# Radio_Robotic_GloveBox_Manipulator.net
KiCad netlist of a schematic drawn in EasyEDA Pro
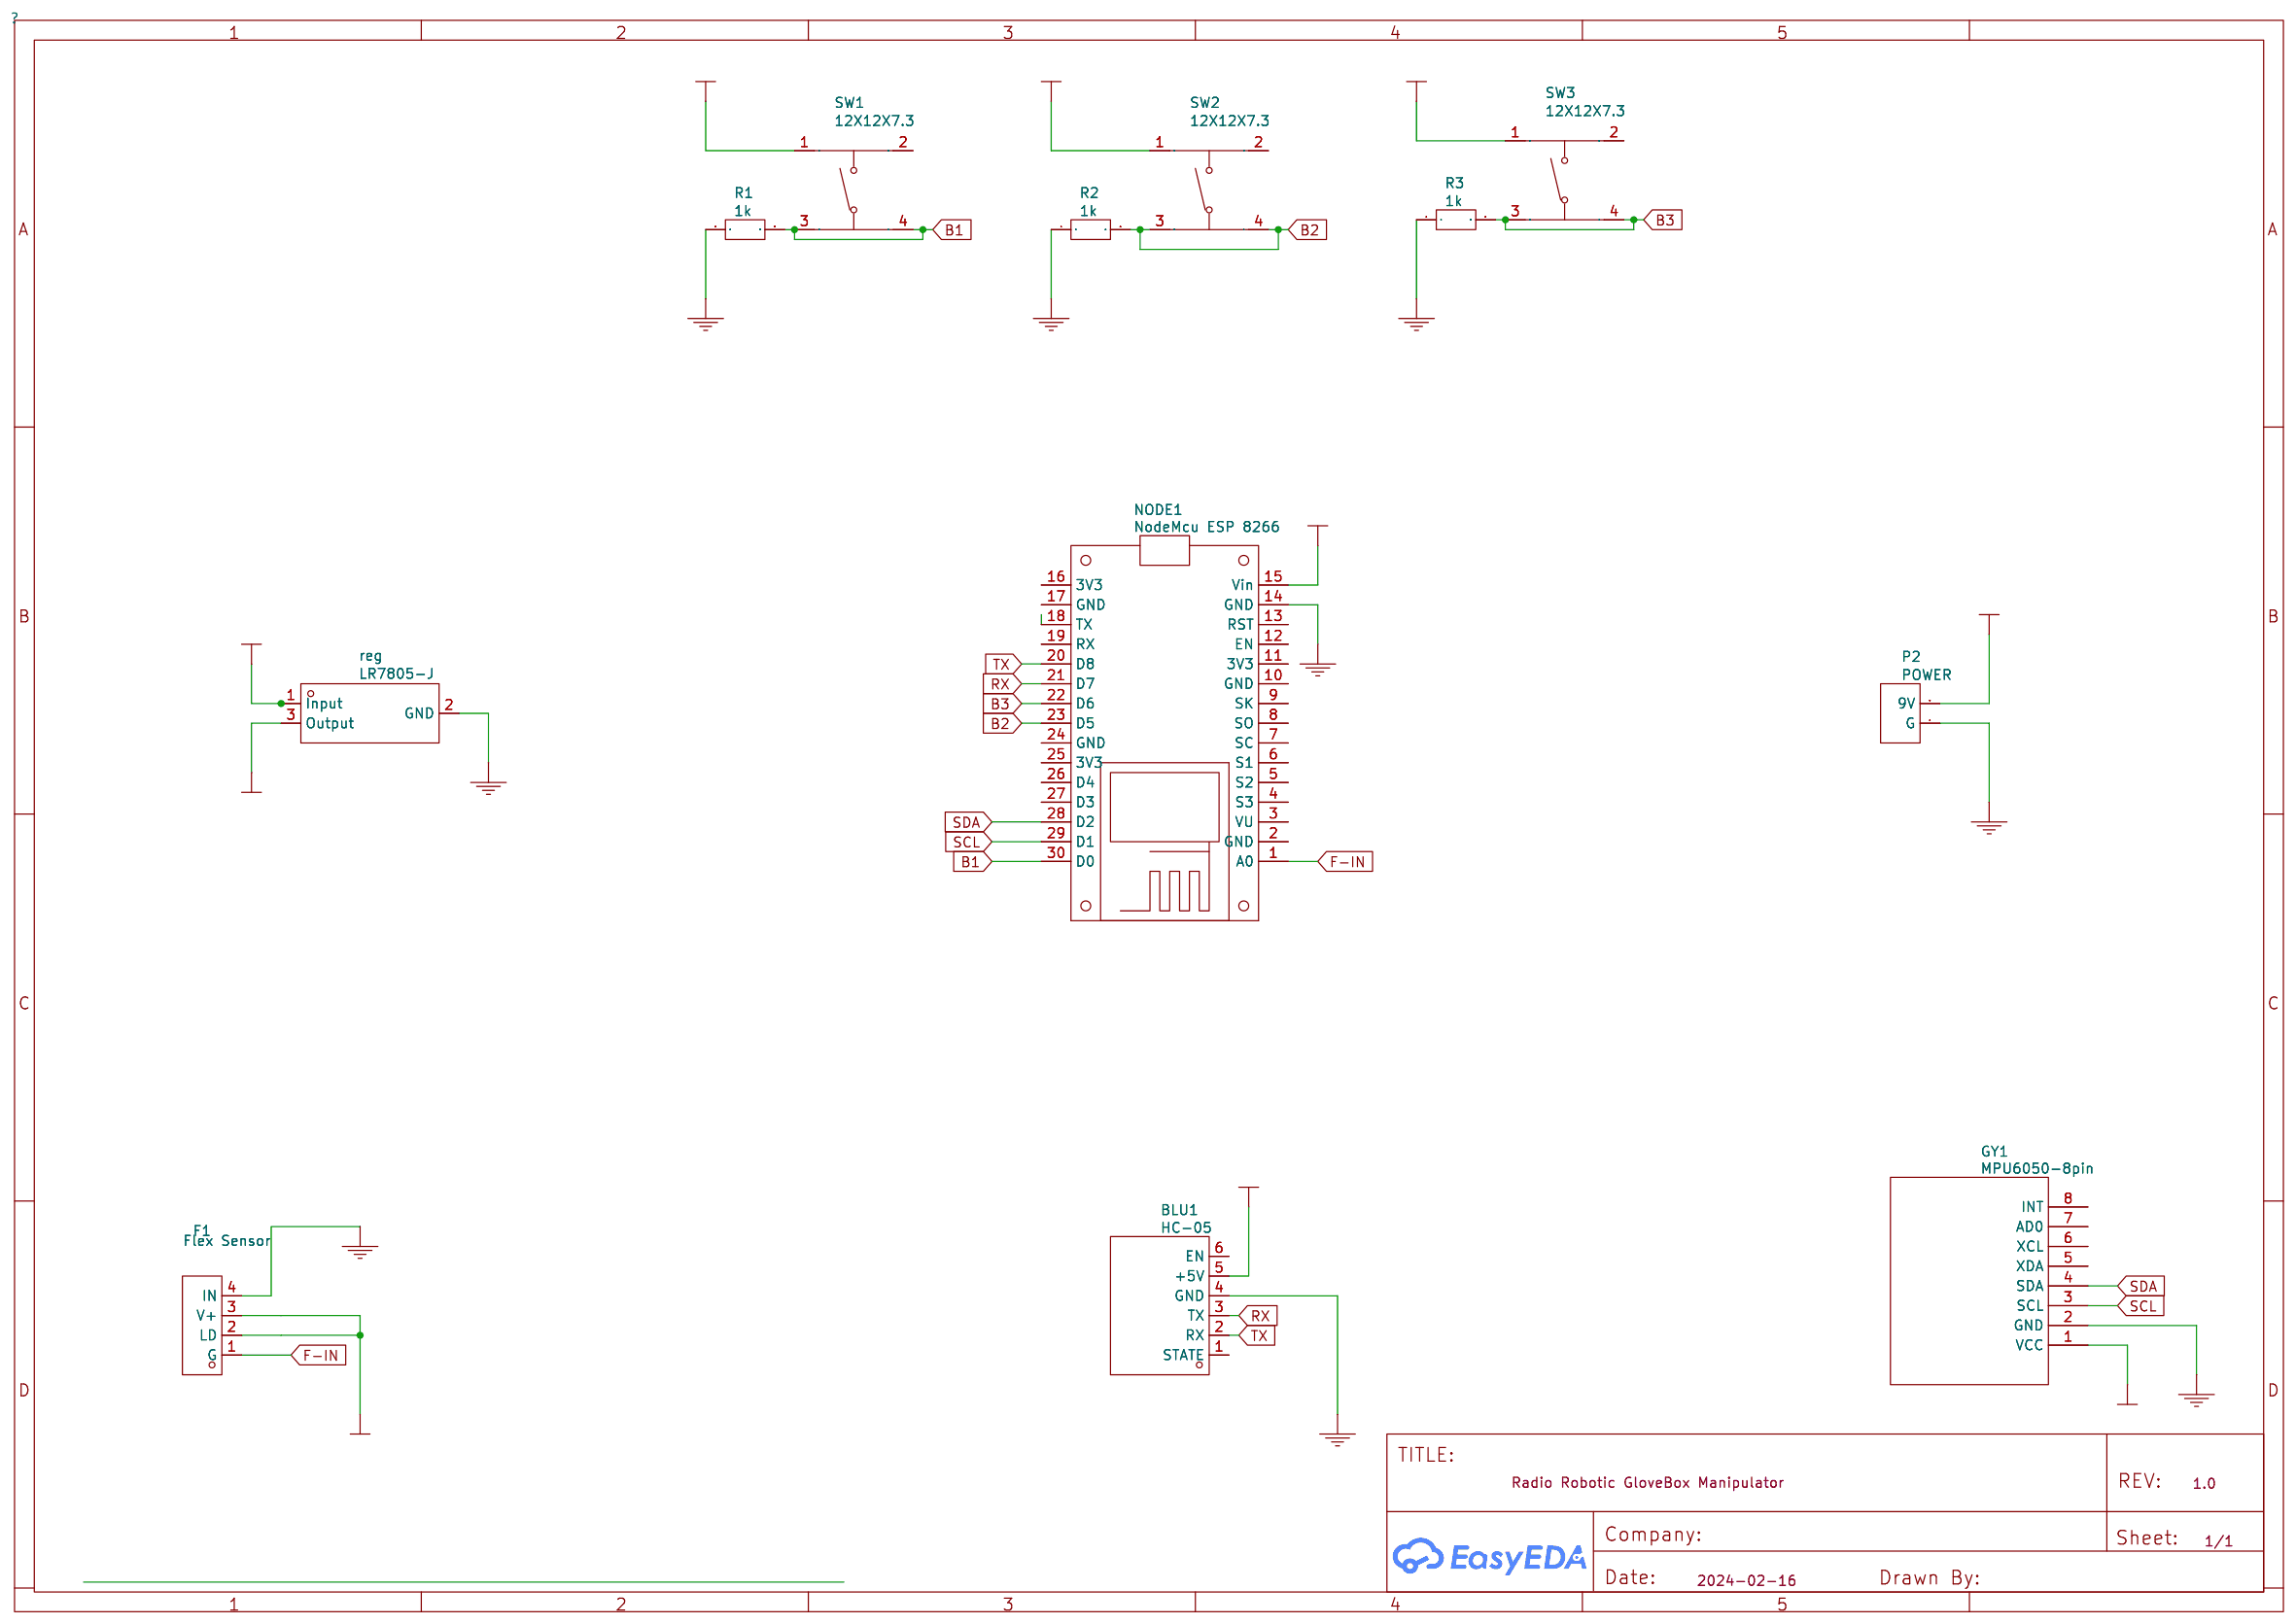
[diagram p0: schematic sheet]

(export (version "E")
  (design (tool "Eeschema 10.0.6"))
  (components
    (comp (ref "BLU1") (value "HC-05") (libsource (lib "easyedapro") (part "HC-05")))
    (comp (ref "F1")
      (value "Flex Sensor")
      (fields
        (field (name "Manufacturer Part") "KH-2FH-1X8P-H4.3")
        (field (name "Manufacturer") "kinghelm(金航标)")
      )
      (libsource (lib "easyedapro") (part "Flex Sensor"))
    )
    (comp (ref "GY1") (value "MPU6050-8pin") (libsource (lib "easyedapro") (part "MPU6050-8pin")))
    (comp (ref "NODE1") (value "NodeMcu ESP 8266") (libsource (lib "easyedapro") (part "NodeMcu ESP 8266")))
    (comp (ref "P2") (value "POWER") (libsource (lib "easyedapro") (part "POWER")))
    (comp (ref "R1") (value "1k") (libsource (lib "easyedapro") (part "1k")))
    (comp (ref "R2") (value "1k") (libsource (lib "easyedapro") (part "1k")))
    (comp (ref "R3") (value "1k") (libsource (lib "easyedapro") (part "1k")))
    (comp (ref "reg")
      (value "LR7805-J")
      (fields (field (name "Manufacturer") "LR(朗瑞)"))
      (libsource (lib "easyedapro") (part "LR7805-J"))
    )
    (comp (ref "SW1")
      (value "12X12X7.3")
      (fields (field (name "Manufacturer Part") "12x12x7.3 黄头") (field (name "Manufacturer") "BOOMELE(博穆精密)"))
      (libsource (lib "easyedapro") (part "12X12X7.3"))
    )
    (comp (ref "SW2")
      (value "12X12X7.3")
      (fields (field (name "Manufacturer Part") "12x12x7.3 黄头") (field (name "Manufacturer") "BOOMELE(博穆精密)"))
      (libsource (lib "easyedapro") (part "12X12X7.3"))
    )
    (comp (ref "SW3")
      (value "12X12X7.3")
      (fields (field (name "Manufacturer Part") "12x12x7.3 黄头") (field (name "Manufacturer") "BOOMELE(博穆精密)"))
      (libsource (lib "easyedapro") (part "12X12X7.3"))
    )
  )
  (nets
    (net (code "1") (name "+5V") (class "Default")
      (node (ref "BLU1") (pin "5") (pinfunction "+5V_5") (pintype "unspecified"))
      (node (ref "F1") (pin "2") (pinfunction "LD_2") (pintype "unspecified"))
      (node (ref "F1") (pin "3") (pinfunction "V+_3") (pintype "unspecified"))
      (node (ref "GY1") (pin "1") (pinfunction "VCC_1") (pintype "unspecified"))
      (node (ref "NODE1") (pin "15") (pinfunction "Vin_15") (pintype "unspecified"))
      (node (ref "SW1") (pin "1") (pinfunction "1_1") (pintype "unspecified"))
      (node (ref "SW2") (pin "1") (pinfunction "1_1") (pintype "unspecified"))
      (node (ref "SW3") (pin "1") (pinfunction "1_1") (pintype "unspecified"))
      (node (ref "reg") (pin "3") (pinfunction "Output_3") (pintype "unspecified"))
    )
    (net (code "2") (name "B1") (class "Default")
      (node (ref "NODE1") (pin "30") (pinfunction "D0_30") (pintype "unspecified"))
      (node (ref "R1") (pin "2") (pinfunction "2_2") (pintype "unspecified"))
      (node (ref "SW1") (pin "3") (pinfunction "3_3") (pintype "unspecified"))
      (node (ref "SW1") (pin "4") (pinfunction "4_4") (pintype "unspecified"))
    )
    (net (code "3") (name "B2") (class "Default")
      (node (ref "NODE1") (pin "23") (pinfunction "D5_23") (pintype "unspecified"))
      (node (ref "R2") (pin "2") (pinfunction "2_2") (pintype "unspecified"))
      (node (ref "SW2") (pin "3") (pinfunction "3_3") (pintype "unspecified"))
      (node (ref "SW2") (pin "4") (pinfunction "4_4") (pintype "unspecified"))
    )
    (net (code "4") (name "B3") (class "Default")
      (node (ref "NODE1") (pin "22") (pinfunction "D6_22") (pintype "unspecified"))
      (node (ref "R3") (pin "2") (pinfunction "2_2") (pintype "unspecified"))
      (node (ref "SW3") (pin "3") (pinfunction "3_3") (pintype "unspecified"))
      (node (ref "SW3") (pin "4") (pinfunction "4_4") (pintype "unspecified"))
    )
    (net (code "5") (name "F-IN") (class "Default")
      (node (ref "F1") (pin "1") (pinfunction "G_1") (pintype "unspecified"))
      (node (ref "NODE1") (pin "1") (pinfunction "A0_1") (pintype "unspecified"))
    )
    (net (code "6") (name "GND") (class "Default")
      (node (ref "BLU1") (pin "4") (pinfunction "GND_4") (pintype "unspecified"))
      (node (ref "F1") (pin "4") (pinfunction "IN_4") (pintype "unspecified"))
      (node (ref "GY1") (pin "2") (pinfunction "GND_2") (pintype "unspecified"))
      (node (ref "NODE1") (pin "14") (pinfunction "GND_14") (pintype "unspecified"))
      (node (ref "P2") (pin "1") (pinfunction "G_1") (pintype "unspecified"))
      (node (ref "R1") (pin "1") (pinfunction "1_1") (pintype "unspecified"))
      (node (ref "R2") (pin "1") (pinfunction "1_1") (pintype "unspecified"))
      (node (ref "R3") (pin "1") (pinfunction "1_1") (pintype "unspecified"))
      (node (ref "reg") (pin "2") (pinfunction "GND_2") (pintype "unspecified"))
    )
    (net (code "7") (name "RX") (class "Default")
      (node (ref "BLU1") (pin "3") (pinfunction "TX_3") (pintype "unspecified"))
      (node (ref "NODE1") (pin "21") (pinfunction "D7_21") (pintype "unspecified"))
    )
    (net (code "8") (name "SCL") (class "Default")
      (node (ref "GY1") (pin "3") (pinfunction "SCL_3") (pintype "unspecified"))
      (node (ref "NODE1") (pin "29") (pinfunction "D1_29") (pintype "unspecified"))
    )
    (net (code "9") (name "SDA") (class "Default")
      (node (ref "GY1") (pin "4") (pinfunction "SDA_4") (pintype "unspecified"))
      (node (ref "NODE1") (pin "28") (pinfunction "D2_28") (pintype "unspecified"))
    )
    (net (code "10") (name "TX") (class "Default")
      (node (ref "BLU1") (pin "2") (pinfunction "RX_2") (pintype "unspecified"))
      (node (ref "NODE1") (pin "20") (pinfunction "D8_20") (pintype "unspecified"))
    )
    (net (code "11") (name "VCC") (class "Default")
      (node (ref "P2") (pin "2") (pinfunction "9V_2") (pintype "unspecified"))
      (node (ref "reg") (pin "1") (pinfunction "Input_1") (pintype "unspecified"))
    )
    (net (code "12") (name "unconnected-(BLU1-EN-Pad6)") (class "Default")
      (node (ref "BLU1") (pin "6") (pinfunction "EN_6") (pintype "unspecified"))
    )
    (net (code "13") (name "unconnected-(BLU1-STATE-Pad1)") (class "Default")
      (node (ref "BLU1") (pin "1") (pinfunction "STATE_1") (pintype "unspecified"))
    )
    (net (code "14") (name "unconnected-(GY1-AD0-Pad7)") (class "Default")
      (node (ref "GY1") (pin "7") (pinfunction "AD0_7") (pintype "unspecified"))
    )
    (net (code "15") (name "unconnected-(GY1-INT-Pad8)") (class "Default")
      (node (ref "GY1") (pin "8") (pinfunction "INT_8") (pintype "unspecified"))
    )
    (net (code "16") (name "unconnected-(GY1-XCL-Pad6)") (class "Default")
      (node (ref "GY1") (pin "6") (pinfunction "XCL_6") (pintype "unspecified"))
    )
    (net (code "17") (name "unconnected-(GY1-XDA-Pad5)") (class "Default")
      (node (ref "GY1") (pin "5") (pinfunction "XDA_5") (pintype "unspecified"))
    )
    (net (code "18") (name "unconnected-(NODE1-3V3-Pad11)") (class "Default")
      (node (ref "NODE1") (pin "11") (pinfunction "3V3_11") (pintype "unspecified"))
    )
    (net (code "19") (name "unconnected-(NODE1-3V3-Pad16)") (class "Default")
      (node (ref "NODE1") (pin "16") (pinfunction "3V3_16") (pintype "unspecified"))
    )
    (net (code "20") (name "unconnected-(NODE1-3V3-Pad25)") (class "Default")
      (node (ref "NODE1") (pin "25") (pinfunction "3V3_25") (pintype "unspecified"))
    )
    (net (code "21") (name "unconnected-(NODE1-D3-Pad27)") (class "Default")
      (node (ref "NODE1") (pin "27") (pinfunction "D3_27") (pintype "unspecified"))
    )
    (net (code "22") (name "unconnected-(NODE1-D4-Pad26)") (class "Default")
      (node (ref "NODE1") (pin "26") (pinfunction "D4_26") (pintype "unspecified"))
    )
    (net (code "23") (name "unconnected-(NODE1-EN-Pad12)") (class "Default")
      (node (ref "NODE1") (pin "12") (pinfunction "EN_12") (pintype "unspecified"))
    )
    (net (code "24") (name "unconnected-(NODE1-GND-Pad2)") (class "Default")
      (node (ref "NODE1") (pin "2") (pinfunction "GND_2") (pintype "unspecified"))
    )
    (net (code "25") (name "unconnected-(NODE1-GND-Pad10)") (class "Default")
      (node (ref "NODE1") (pin "10") (pinfunction "GND_10") (pintype "unspecified"))
    )
    (net (code "26") (name "unconnected-(NODE1-GND-Pad17)") (class "Default")
      (node (ref "NODE1") (pin "17") (pinfunction "GND_17") (pintype "unspecified"))
    )
    (net (code "27") (name "unconnected-(NODE1-GND-Pad24)") (class "Default")
      (node (ref "NODE1") (pin "24") (pinfunction "GND_24") (pintype "unspecified"))
    )
    (net (code "28") (name "unconnected-(NODE1-RST-Pad13)") (class "Default")
      (node (ref "NODE1") (pin "13") (pinfunction "RST_13") (pintype "unspecified"))
    )
    (net (code "29") (name "unconnected-(NODE1-RX-Pad19)") (class "Default")
      (node (ref "NODE1") (pin "19") (pinfunction "RX_19") (pintype "unspecified"))
    )
    (net (code "30") (name "unconnected-(NODE1-S1-Pad6)") (class "Default")
      (node (ref "NODE1") (pin "6") (pinfunction "S1_6") (pintype "unspecified"))
    )
    (net (code "31") (name "unconnected-(NODE1-S2-Pad5)") (class "Default")
      (node (ref "NODE1") (pin "5") (pinfunction "S2_5") (pintype "unspecified"))
    )
    (net (code "32") (name "unconnected-(NODE1-S3-Pad4)") (class "Default")
      (node (ref "NODE1") (pin "4") (pinfunction "S3_4") (pintype "unspecified"))
    )
    (net (code "33") (name "unconnected-(NODE1-SC-Pad7)") (class "Default")
      (node (ref "NODE1") (pin "7") (pinfunction "SC_7") (pintype "unspecified"))
    )
    (net (code "34") (name "unconnected-(NODE1-SK-Pad9)") (class "Default")
      (node (ref "NODE1") (pin "9") (pinfunction "SK_9") (pintype "unspecified"))
    )
    (net (code "35") (name "unconnected-(NODE1-SO-Pad8)") (class "Default")
      (node (ref "NODE1") (pin "8") (pinfunction "SO_8") (pintype "unspecified"))
    )
    (net (code "36") (name "unconnected-(NODE1-TX-Pad18)") (class "Default")
      (node (ref "NODE1") (pin "18") (pinfunction "TX_18") (pintype "unspecified"))
    )
    (net (code "37") (name "unconnected-(NODE1-VU-Pad3)") (class "Default")
      (node (ref "NODE1") (pin "3") (pinfunction "VU_3") (pintype "unspecified"))
    )
    (net (code "38") (name "unconnected-(SW1-Pad2)") (class "Default")
      (node (ref "SW1") (pin "2") (pinfunction "2_2") (pintype "unspecified"))
    )
    (net (code "39") (name "unconnected-(SW2-Pad2)") (class "Default")
      (node (ref "SW2") (pin "2") (pinfunction "2_2") (pintype "unspecified"))
    )
    (net (code "40") (name "unconnected-(SW3-Pad2)") (class "Default")
      (node (ref "SW3") (pin "2") (pinfunction "2_2") (pintype "unspecified"))
    )
  )
)
